# GroundStationCR.net
KiCad netlist of a schematic drawn in EAGLE
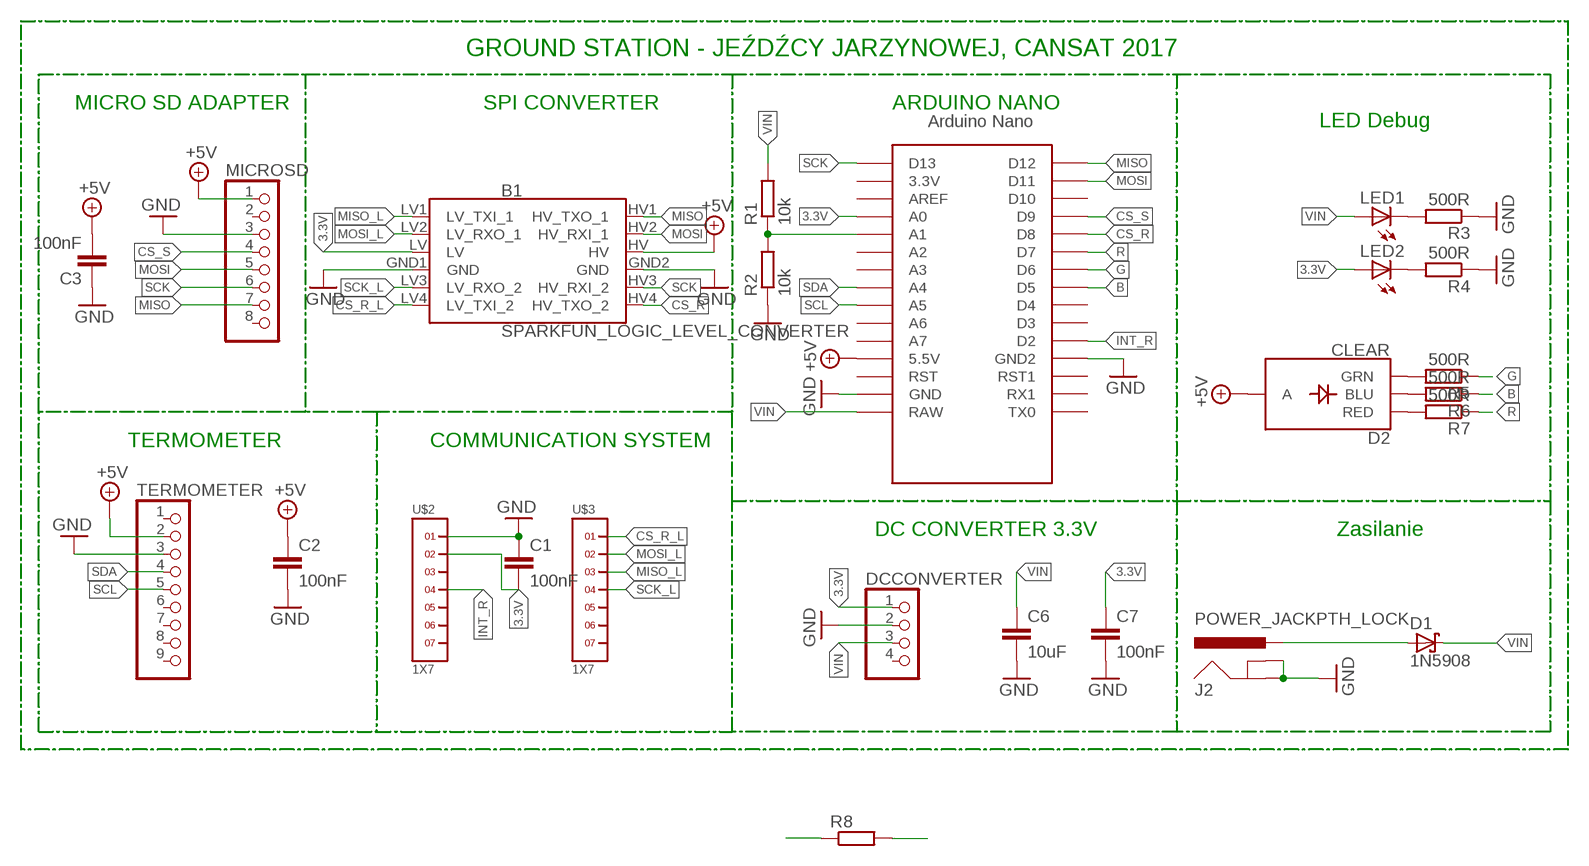
[diagram p0: schematic, sheet 1]

(export (version "E")
  (design (tool "Eeschema 10.0.6"))
  (components
    (comp (ref "B1")
      (value "SPARKFUN_LOGIC_LEVEL_CONVERTER")
      (footprint "eagle-import:SPARKFUN_LOGIC_LEVEL_CONVERTER")
      (libsource (lib "eagle-import") (part "SPARKFUN_LOGIC_LEVEL_CONVERTER"))
    )
    (comp (ref "C1")
      (value "100nF")
      (footprint "eagle-import:C050-025X075")
      (libsource (lib "eagle-import") (part "C-EU050-025X075"))
    )
    (comp (ref "C2")
      (value "100nF")
      (footprint "eagle-import:C050-025X075")
      (libsource (lib "eagle-import") (part "C-EU050-025X075"))
    )
    (comp (ref "C3")
      (value "100nF")
      (footprint "eagle-import:C050-025X075")
      (libsource (lib "eagle-import") (part "C-EU050-025X075"))
    )
    (comp (ref "C6")
      (value "10uF")
      (footprint "eagle-import:C050-025X075")
      (libsource (lib "eagle-import") (part "C-EU050-025X075"))
    )
    (comp (ref "C7")
      (value "100nF")
      (footprint "eagle-import:C050-025X075")
      (libsource (lib "eagle-import") (part "C-EU050-025X075"))
    )
    (comp (ref "D1")
      (value "1N5908")
      (footprint "eagle-import:C4111-15")
      (libsource (lib "eagle-import") (part "1N5908"))
    )
    (comp (ref "D2")
      (value "CLEAR")
      (footprint "eagle-import:LED-RGB-THRU")
      (libsource (lib "eagle-import") (part "LED-RGB-CACLEAR"))
    )
    (comp (ref "DCCONVERTER")
      (value "PINHD-1X4")
      (footprint "eagle-import:1X04")
      (libsource (lib "eagle-import") (part "PINHD-1X4"))
    )
    (comp (ref "J2")
      (value "POWER_JACKPTH_LOCK")
      (footprint "eagle-import:POWER_JACK_PTH_LOCK")
      (libsource (lib "eagle-import") (part "POWER_JACKPTH_LOCK"))
    )
    (comp (ref "LED1")
      (value "LED3MM")
      (footprint "eagle-import:LED3MM")
      (libsource (lib "eagle-import") (part "LED3MM"))
    )
    (comp (ref "LED2")
      (value "LED3MM")
      (footprint "eagle-import:LED3MM")
      (libsource (lib "eagle-import") (part "LED3MM"))
    )
    (comp (ref "MICROSD")
      (value "PINHD-1X8")
      (footprint "eagle-import:1X08")
      (libsource (lib "eagle-import") (part "PINHD-1X8"))
    )
    (comp (ref "R1")
      (value "10k")
      (footprint "eagle-import:0207_7")
      (libsource (lib "eagle-import") (part "R-EU_0207/7"))
    )
    (comp (ref "R2")
      (value "10k")
      (footprint "eagle-import:0207_7")
      (libsource (lib "eagle-import") (part "R-EU_0207/7"))
    )
    (comp (ref "R3")
      (value "500R")
      (footprint "eagle-import:0207_7")
      (libsource (lib "eagle-import") (part "R-EU_0207/7"))
    )
    (comp (ref "R4")
      (value "500R")
      (footprint "eagle-import:0207_7")
      (libsource (lib "eagle-import") (part "R-EU_0207/7"))
    )
    (comp (ref "R5")
      (value "500R")
      (footprint "eagle-import:0207_7")
      (libsource (lib "eagle-import") (part "R-EU_0207/7"))
    )
    (comp (ref "R6")
      (value "500R")
      (footprint "eagle-import:0207_7")
      (libsource (lib "eagle-import") (part "R-EU_0207/7"))
    )
    (comp (ref "R7")
      (value "500R")
      (footprint "eagle-import:0207_7")
      (libsource (lib "eagle-import") (part "R-EU_0207/7"))
    )
    (comp (ref "R8")
      (value "R-EU_0207/5V")
      (footprint "eagle-import:0207_5V")
      (libsource (lib "eagle-import") (part "R-EU_0207/5V"))
    )
    (comp (ref "TERMOMETER")
      (value "PINHD-1X9")
      (footprint "eagle-import:1X09")
      (libsource (lib "eagle-import") (part "PINHD-1X9"))
    )
    (comp (ref "U$1")
      (value "NANO")
      (footprint "eagle-import:NANO")
      (libsource (lib "eagle-import") (part "NANO"))
    )
    (comp (ref "U$2")
      (value "1X7")
      (footprint "eagle-import:1X7")
      (libsource (lib "eagle-import") (part "1X7"))
    )
    (comp (ref "U$3")
      (value "1X7")
      (footprint "eagle-import:1X7")
      (libsource (lib "eagle-import") (part "1X7"))
    )
  )
  (nets
    (net (code "1") (name "+5V") (class "Default")
      (node (ref "B1") (pin "HV") (pinfunction "HV_HV") (pintype "power_in"))
      (node (ref "C2") (pin "1") (pinfunction "1_1") (pintype "passive"))
      (node (ref "C3") (pin "2") (pinfunction "2_2") (pintype "passive"))
      (node (ref "D2") (pin "2") (pinfunction "A_2") (pintype "bidirectional"))
      (node (ref "MICROSD") (pin "1") (pinfunction "1_1") (pintype "passive"))
      (node (ref "TERMOMETER") (pin "2") (pinfunction "2_2") (pintype "passive"))
      (node (ref "U$1") (pin "5V") (pinfunction "5.5V_5V") (pintype "bidirectional"))
    )
    (net (code "2") (name "3.3V") (class "Default")
      (node (ref "B1") (pin "LV") (pinfunction "LV_LV") (pintype "power_in"))
      (node (ref "C1") (pin "2") (pinfunction "2_2") (pintype "passive"))
      (node (ref "C7") (pin "1") (pinfunction "1_1") (pintype "passive"))
      (node (ref "DCCONVERTER") (pin "1") (pinfunction "1_1") (pintype "passive"))
      (node (ref "LED2") (pin "A") (pinfunction "A_A") (pintype "passive"))
      (node (ref "U$1") (pin "A0") (pinfunction "A0_A0") (pintype "bidirectional"))
      (node (ref "U$2") (pin "2") (pinfunction "2_2") (pintype "bidirectional"))
    )
    (net (code "3") (name "B") (class "Default")
      (node (ref "R6") (pin "1") (pinfunction "1_1") (pintype "passive"))
      (node (ref "U$1") (pin "D5") (pinfunction "D5_D5") (pintype "bidirectional"))
    )
    (net (code "4") (name "CS_R") (class "Default")
      (node (ref "B1") (pin "HV4") (pinfunction "HV_TXO_2_HV4") (pintype "bidirectional"))
      (node (ref "U$1") (pin "D8") (pinfunction "D8_D8") (pintype "bidirectional"))
    )
    (net (code "5") (name "CS_R_L") (class "Default")
      (node (ref "B1") (pin "LV4") (pinfunction "LV_TXI_2_LV4") (pintype "bidirectional"))
      (node (ref "U$3") (pin "1") (pinfunction "1_1") (pintype "bidirectional"))
    )
    (net (code "6") (name "CS_S") (class "Default")
      (node (ref "MICROSD") (pin "4") (pinfunction "4_4") (pintype "passive"))
      (node (ref "U$1") (pin "D9") (pinfunction "D9_D9") (pintype "bidirectional"))
    )
    (net (code "7") (name "G") (class "Default")
      (node (ref "R5") (pin "1") (pinfunction "1_1") (pintype "passive"))
      (node (ref "U$1") (pin "D6") (pinfunction "D6_D6") (pintype "bidirectional"))
    )
    (net (code "8") (name "GND") (class "Default")
      (node (ref "B1") (pin "GND1") (pinfunction "GND_GND1") (pintype "power_in"))
      (node (ref "B1") (pin "GND2") (pinfunction "GND_GND2") (pintype "power_in"))
      (node (ref "C1") (pin "1") (pinfunction "1_1") (pintype "passive"))
      (node (ref "C2") (pin "2") (pinfunction "2_2") (pintype "passive"))
      (node (ref "C3") (pin "1") (pinfunction "1_1") (pintype "passive"))
      (node (ref "C6") (pin "2") (pinfunction "2_2") (pintype "passive"))
      (node (ref "C7") (pin "2") (pinfunction "2_2") (pintype "passive"))
      (node (ref "DCCONVERTER") (pin "2") (pinfunction "2_2") (pintype "passive"))
      (node (ref "J2") (pin "GND") (pinfunction "GND_GND") (pintype "bidirectional"))
      (node (ref "J2") (pin "GNDBREAK") (pinfunction "GNDBREAK_GNDBREAK") (pintype "bidirectional"))
      (node (ref "MICROSD") (pin "3") (pinfunction "3_3") (pintype "passive"))
      (node (ref "R2") (pin "1") (pinfunction "1_1") (pintype "passive"))
      (node (ref "R3") (pin "1") (pinfunction "1_1") (pintype "passive"))
      (node (ref "R4") (pin "1") (pinfunction "1_1") (pintype "passive"))
      (node (ref "TERMOMETER") (pin "3") (pinfunction "3_3") (pintype "passive"))
      (node (ref "U$1") (pin "GND") (pinfunction "GND_GND") (pintype "bidirectional"))
      (node (ref "U$1") (pin "GND1") (pinfunction "GND2_GND1") (pintype "bidirectional"))
      (node (ref "U$2") (pin "1") (pinfunction "1_1") (pintype "bidirectional"))
    )
    (net (code "9") (name "INT_R") (class "Default")
      (node (ref "U$1") (pin "D2") (pinfunction "D2_D2") (pintype "bidirectional"))
      (node (ref "U$2") (pin "4") (pinfunction "4_4") (pintype "bidirectional"))
    )
    (net (code "10") (name "MISO") (class "Default")
      (node (ref "B1") (pin "HV1") (pinfunction "HV_TXO_1_HV1") (pintype "bidirectional"))
      (node (ref "MICROSD") (pin "7") (pinfunction "7_7") (pintype "passive"))
      (node (ref "R8") (pin "1") (pinfunction "1_1") (pintype "passive"))
      (node (ref "R8") (pin "2") (pinfunction "2_2") (pintype "passive"))
      (node (ref "U$1") (pin "D12") (pinfunction "D12_D12") (pintype "bidirectional"))
    )
    (net (code "11") (name "MISO_L") (class "Default")
      (node (ref "B1") (pin "LV1") (pinfunction "LV_TXI_1_LV1") (pintype "bidirectional"))
      (node (ref "U$3") (pin "3") (pinfunction "3_3") (pintype "bidirectional"))
    )
    (net (code "12") (name "MOSI") (class "Default")
      (node (ref "B1") (pin "HV2") (pinfunction "HV_RXI_1_HV2") (pintype "bidirectional"))
      (node (ref "MICROSD") (pin "5") (pinfunction "5_5") (pintype "passive"))
      (node (ref "U$1") (pin "D11") (pinfunction "D11_D11") (pintype "bidirectional"))
    )
    (net (code "13") (name "MOSI_L") (class "Default")
      (node (ref "B1") (pin "LV2") (pinfunction "LV_RXO_1_LV2") (pintype "bidirectional"))
      (node (ref "U$3") (pin "2") (pinfunction "2_2") (pintype "bidirectional"))
    )
    (net (code "14") (name "Net-(D1-PadA)") (class "Default")
      (node (ref "D1") (pin "A") (pinfunction "A_A") (pintype "passive"))
      (node (ref "J2") (pin "PWR") (pinfunction "PWR_PWR") (pintype "bidirectional"))
    )
    (net (code "15") (name "Net-(D2-BLU)") (class "Default")
      (node (ref "D2") (pin "4") (pinfunction "BLU_4") (pintype "bidirectional"))
      (node (ref "R6") (pin "2") (pinfunction "2_2") (pintype "passive"))
    )
    (net (code "16") (name "Net-(D2-GRN)") (class "Default")
      (node (ref "D2") (pin "3") (pinfunction "GRN_3") (pintype "bidirectional"))
      (node (ref "R5") (pin "2") (pinfunction "2_2") (pintype "passive"))
    )
    (net (code "17") (name "Net-(D2-RED)") (class "Default")
      (node (ref "D2") (pin "1") (pinfunction "RED_1") (pintype "bidirectional"))
      (node (ref "R7") (pin "2") (pinfunction "2_2") (pintype "passive"))
    )
    (net (code "18") (name "Net-(LED1-C)") (class "Default")
      (node (ref "LED1") (pin "K") (pinfunction "C_K") (pintype "passive"))
      (node (ref "R3") (pin "2") (pinfunction "2_2") (pintype "passive"))
    )
    (net (code "19") (name "Net-(LED2-C)") (class "Default")
      (node (ref "LED2") (pin "K") (pinfunction "C_K") (pintype "passive"))
      (node (ref "R4") (pin "2") (pinfunction "2_2") (pintype "passive"))
    )
    (net (code "20") (name "Net-(R1-Pad1)") (class "Default")
      (node (ref "R1") (pin "1") (pinfunction "1_1") (pintype "passive"))
      (node (ref "R2") (pin "2") (pinfunction "2_2") (pintype "passive"))
      (node (ref "U$1") (pin "A1") (pinfunction "A1_A1") (pintype "bidirectional"))
    )
    (net (code "21") (name "R") (class "Default")
      (node (ref "R7") (pin "1") (pinfunction "1_1") (pintype "passive"))
      (node (ref "U$1") (pin "D7") (pinfunction "D7_D7") (pintype "bidirectional"))
    )
    (net (code "22") (name "SCK") (class "Default")
      (node (ref "B1") (pin "HV3") (pinfunction "HV_RXI_2_HV3") (pintype "bidirectional"))
      (node (ref "MICROSD") (pin "6") (pinfunction "6_6") (pintype "passive"))
      (node (ref "U$1") (pin "D13") (pinfunction "D13_D13") (pintype "bidirectional"))
    )
    (net (code "23") (name "SCK_L") (class "Default")
      (node (ref "B1") (pin "LV3") (pinfunction "LV_RXO_2_LV3") (pintype "bidirectional"))
      (node (ref "U$3") (pin "4") (pinfunction "4_4") (pintype "bidirectional"))
    )
    (net (code "24") (name "SCL") (class "Default")
      (node (ref "TERMOMETER") (pin "5") (pinfunction "5_5") (pintype "passive"))
      (node (ref "U$1") (pin "A5") (pinfunction "A5_A5") (pintype "bidirectional"))
    )
    (net (code "25") (name "SDA") (class "Default")
      (node (ref "TERMOMETER") (pin "4") (pinfunction "4_4") (pintype "passive"))
      (node (ref "U$1") (pin "A4") (pinfunction "A4_A4") (pintype "bidirectional"))
    )
    (net (code "26") (name "VIN") (class "Default")
      (node (ref "C6") (pin "1") (pinfunction "1_1") (pintype "passive"))
      (node (ref "D1") (pin "C") (pinfunction "C_C") (pintype "passive"))
      (node (ref "DCCONVERTER") (pin "3") (pinfunction "3_3") (pintype "passive"))
      (node (ref "LED1") (pin "A") (pinfunction "A_A") (pintype "passive"))
      (node (ref "R1") (pin "2") (pinfunction "2_2") (pintype "passive"))
      (node (ref "U$1") (pin "RAW") (pinfunction "RAW_RAW") (pintype "bidirectional"))
    )
    (net (code "27") (name "unconnected-(DCCONVERTER-Pad4)") (class "Default")
      (node (ref "DCCONVERTER") (pin "4") (pinfunction "4_4") (pintype "passive"))
    )
    (net (code "28") (name "unconnected-(MICROSD-Pad2)") (class "Default")
      (node (ref "MICROSD") (pin "2") (pinfunction "2_2") (pintype "passive"))
    )
    (net (code "29") (name "unconnected-(MICROSD-Pad8)") (class "Default")
      (node (ref "MICROSD") (pin "8") (pinfunction "8_8") (pintype "passive"))
    )
    (net (code "30") (name "unconnected-(TERMOMETER-Pad1)") (class "Default")
      (node (ref "TERMOMETER") (pin "1") (pinfunction "1_1") (pintype "passive"))
    )
    (net (code "31") (name "unconnected-(TERMOMETER-Pad6)") (class "Default")
      (node (ref "TERMOMETER") (pin "6") (pinfunction "6_6") (pintype "passive"))
    )
    (net (code "32") (name "unconnected-(TERMOMETER-Pad7)") (class "Default")
      (node (ref "TERMOMETER") (pin "7") (pinfunction "7_7") (pintype "passive"))
    )
    (net (code "33") (name "unconnected-(TERMOMETER-Pad8)") (class "Default")
      (node (ref "TERMOMETER") (pin "8") (pinfunction "8_8") (pintype "passive"))
    )
    (net (code "34") (name "unconnected-(TERMOMETER-Pad9)") (class "Default")
      (node (ref "TERMOMETER") (pin "9") (pinfunction "9_9") (pintype "passive"))
    )
    (net (code "35") (name "unconnected-(U$1-Pad3.3V)") (class "Default")
      (node (ref "U$1") (pin "3.3V") (pinfunction "3.3V_3.3V") (pintype "bidirectional"))
    )
    (net (code "36") (name "unconnected-(U$1-PadA2)") (class "Default")
      (node (ref "U$1") (pin "A2") (pinfunction "A2_A2") (pintype "bidirectional"))
    )
    (net (code "37") (name "unconnected-(U$1-PadA3)") (class "Default")
      (node (ref "U$1") (pin "A3") (pinfunction "A3_A3") (pintype "bidirectional"))
    )
    (net (code "38") (name "unconnected-(U$1-PadA6)") (class "Default")
      (node (ref "U$1") (pin "A6") (pinfunction "A6_A6") (pintype "bidirectional"))
    )
    (net (code "39") (name "unconnected-(U$1-PadA7)") (class "Default")
      (node (ref "U$1") (pin "A7") (pinfunction "A7_A7") (pintype "bidirectional"))
    )
    (net (code "40") (name "unconnected-(U$1-PadAREF)") (class "Default")
      (node (ref "U$1") (pin "AREF") (pinfunction "AREF_AREF") (pintype "bidirectional"))
    )
    (net (code "41") (name "unconnected-(U$1-PadD3)") (class "Default")
      (node (ref "U$1") (pin "D3") (pinfunction "D3_D3") (pintype "bidirectional"))
    )
    (net (code "42") (name "unconnected-(U$1-PadD4)") (class "Default")
      (node (ref "U$1") (pin "D4") (pinfunction "D4_D4") (pintype "bidirectional"))
    )
    (net (code "43") (name "unconnected-(U$1-PadD10)") (class "Default")
      (node (ref "U$1") (pin "D10") (pinfunction "D10_D10") (pintype "bidirectional"))
    )
    (net (code "44") (name "unconnected-(U$1-PadICSP1)") (class "Default")
      (node (ref "U$1") (pin "ICSP1") (pinfunction "ICSP1_ICSP1") (pintype "bidirectional"))
    )
    (net (code "45") (name "unconnected-(U$1-PadICSP2)") (class "Default")
      (node (ref "U$1") (pin "ICSP2") (pinfunction "ICSP2_ICSP2") (pintype "bidirectional"))
    )
    (net (code "46") (name "unconnected-(U$1-PadICSP3)") (class "Default")
      (node (ref "U$1") (pin "ICSP3") (pinfunction "ICSP3_ICSP3") (pintype "bidirectional"))
    )
    (net (code "47") (name "unconnected-(U$1-PadICSP4)") (class "Default")
      (node (ref "U$1") (pin "ICSP4") (pinfunction "ICSP4_ICSP4") (pintype "bidirectional"))
    )
    (net (code "48") (name "unconnected-(U$1-PadICSP5)") (class "Default")
      (node (ref "U$1") (pin "ICSP5") (pinfunction "ICSP5_ICSP5") (pintype "bidirectional"))
    )
    (net (code "49") (name "unconnected-(U$1-PadICSP6)") (class "Default")
      (node (ref "U$1") (pin "ICSP6") (pinfunction "ICSP6_ICSP6") (pintype "bidirectional"))
    )
    (net (code "50") (name "unconnected-(U$1-PadRST)") (class "Default")
      (node (ref "U$1") (pin "RST") (pinfunction "RST_RST") (pintype "bidirectional"))
    )
    (net (code "51") (name "unconnected-(U$1-PadRST1)") (class "Default")
      (node (ref "U$1") (pin "RST1") (pinfunction "RST1_RST1") (pintype "bidirectional"))
    )
    (net (code "52") (name "unconnected-(U$1-PadRX1)") (class "Default")
      (node (ref "U$1") (pin "RX1") (pinfunction "RX1_RX1") (pintype "bidirectional"))
    )
    (net (code "53") (name "unconnected-(U$1-PadTX0)") (class "Default")
      (node (ref "U$1") (pin "TX0") (pinfunction "TX0_TX0") (pintype "bidirectional"))
    )
    (net (code "54") (name "unconnected-(U$2-Pad3)") (class "Default")
      (node (ref "U$2") (pin "3") (pinfunction "3_3") (pintype "bidirectional"))
    )
    (net (code "55") (name "unconnected-(U$2-Pad5)") (class "Default")
      (node (ref "U$2") (pin "5") (pinfunction "5_5") (pintype "bidirectional"))
    )
    (net (code "56") (name "unconnected-(U$2-Pad6)") (class "Default")
      (node (ref "U$2") (pin "6") (pinfunction "6_6") (pintype "bidirectional"))
    )
    (net (code "57") (name "unconnected-(U$2-Pad7)") (class "Default")
      (node (ref "U$2") (pin "7") (pinfunction "7_7") (pintype "bidirectional"))
    )
    (net (code "58") (name "unconnected-(U$3-Pad5)") (class "Default")
      (node (ref "U$3") (pin "5") (pinfunction "5_5") (pintype "bidirectional"))
    )
    (net (code "59") (name "unconnected-(U$3-Pad6)") (class "Default")
      (node (ref "U$3") (pin "6") (pinfunction "6_6") (pintype "bidirectional"))
    )
    (net (code "60") (name "unconnected-(U$3-Pad7)") (class "Default")
      (node (ref "U$3") (pin "7") (pinfunction "7_7") (pintype "bidirectional"))
    )
  )
)
